# hyb.net
KiCad netlist of a schematic drawn in Altium Designer
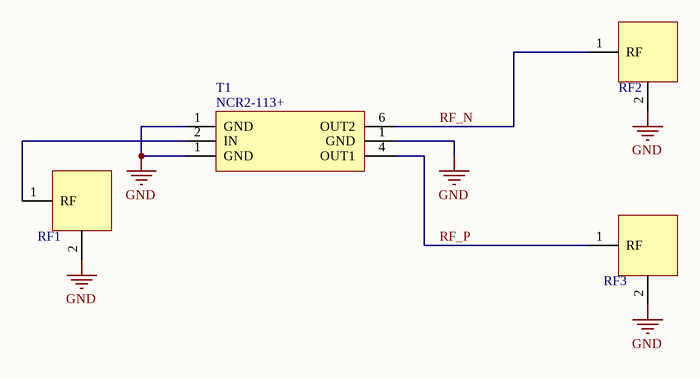
[diagram p0: hyb.SchDoc]

(export (version "E")
  (design (tool "Eeschema 10.0.6"))
  (components
    (comp (ref "RF1")
      (value "SMA Coaxial 50 ohm")
      (footprint "SMA Coaxial 50 ohm")
      (description "142-0701-801")
      (libsource (lib "rf") (part "SMA Coaxial 50 ohm"))
    )
    (comp (ref "RF2")
      (value "SMA Coaxial 50 ohm")
      (footprint "SMA Coaxial 50 ohm")
      (description "142-0701-801")
      (libsource (lib "rf") (part "SMA Coaxial 50 ohm"))
    )
    (comp (ref "RF3")
      (value "SMA Coaxial 50 ohm")
      (footprint "SMA Coaxial 50 ohm")
      (description "142-0701-801")
      (libsource (lib "rf") (part "SMA Coaxial 50 ohm"))
    )
    (comp (ref "T1")
      (value "NCR2-113")
      (footprint "NCR2-Series")
      (description "3.5-11 GHz balun (180), smd")
      (fields (field (name "PARTNUMBER") "NCR2-113+"))
      (libsource (lib "rf") (part "NCR2-113"))
    )
  )
  (nets
    (net (code "1") (name "/RF_N") (class "Default")
      (node (ref "RF2") (pin "1") (pinfunction "RF_1") (pintype "passive"))
      (node (ref "T1") (pin "6") (pinfunction "OUT2_6") (pintype "passive"))
    )
    (net (code "2") (name "/RF_P") (class "Default")
      (node (ref "RF3") (pin "1") (pinfunction "RF_1") (pintype "passive"))
      (node (ref "T1") (pin "4") (pinfunction "OUT1_4") (pintype "passive"))
    )
    (net (code "3") (name "GND") (class "Default")
      (node (ref "RF1") (pin "2") (pinfunction "GND_2") (pintype "passive"))
      (node (ref "RF2") (pin "2") (pinfunction "GND_2") (pintype "passive"))
      (node (ref "RF3") (pin "2") (pinfunction "GND_2") (pintype "passive"))
      (node (ref "T1") (pin "1") (pinfunction "GND_1") (pintype "passive"))
    )
    (net (code "4") (name "Net-(RF1-RF)") (class "Default")
      (node (ref "RF1") (pin "1") (pinfunction "RF_1") (pintype "passive"))
      (node (ref "T1") (pin "2") (pinfunction "IN_2") (pintype "passive"))
    )
  )
)
